# fresh_air_control.net
KiCad netlist of a schematic drawn in EAGLE
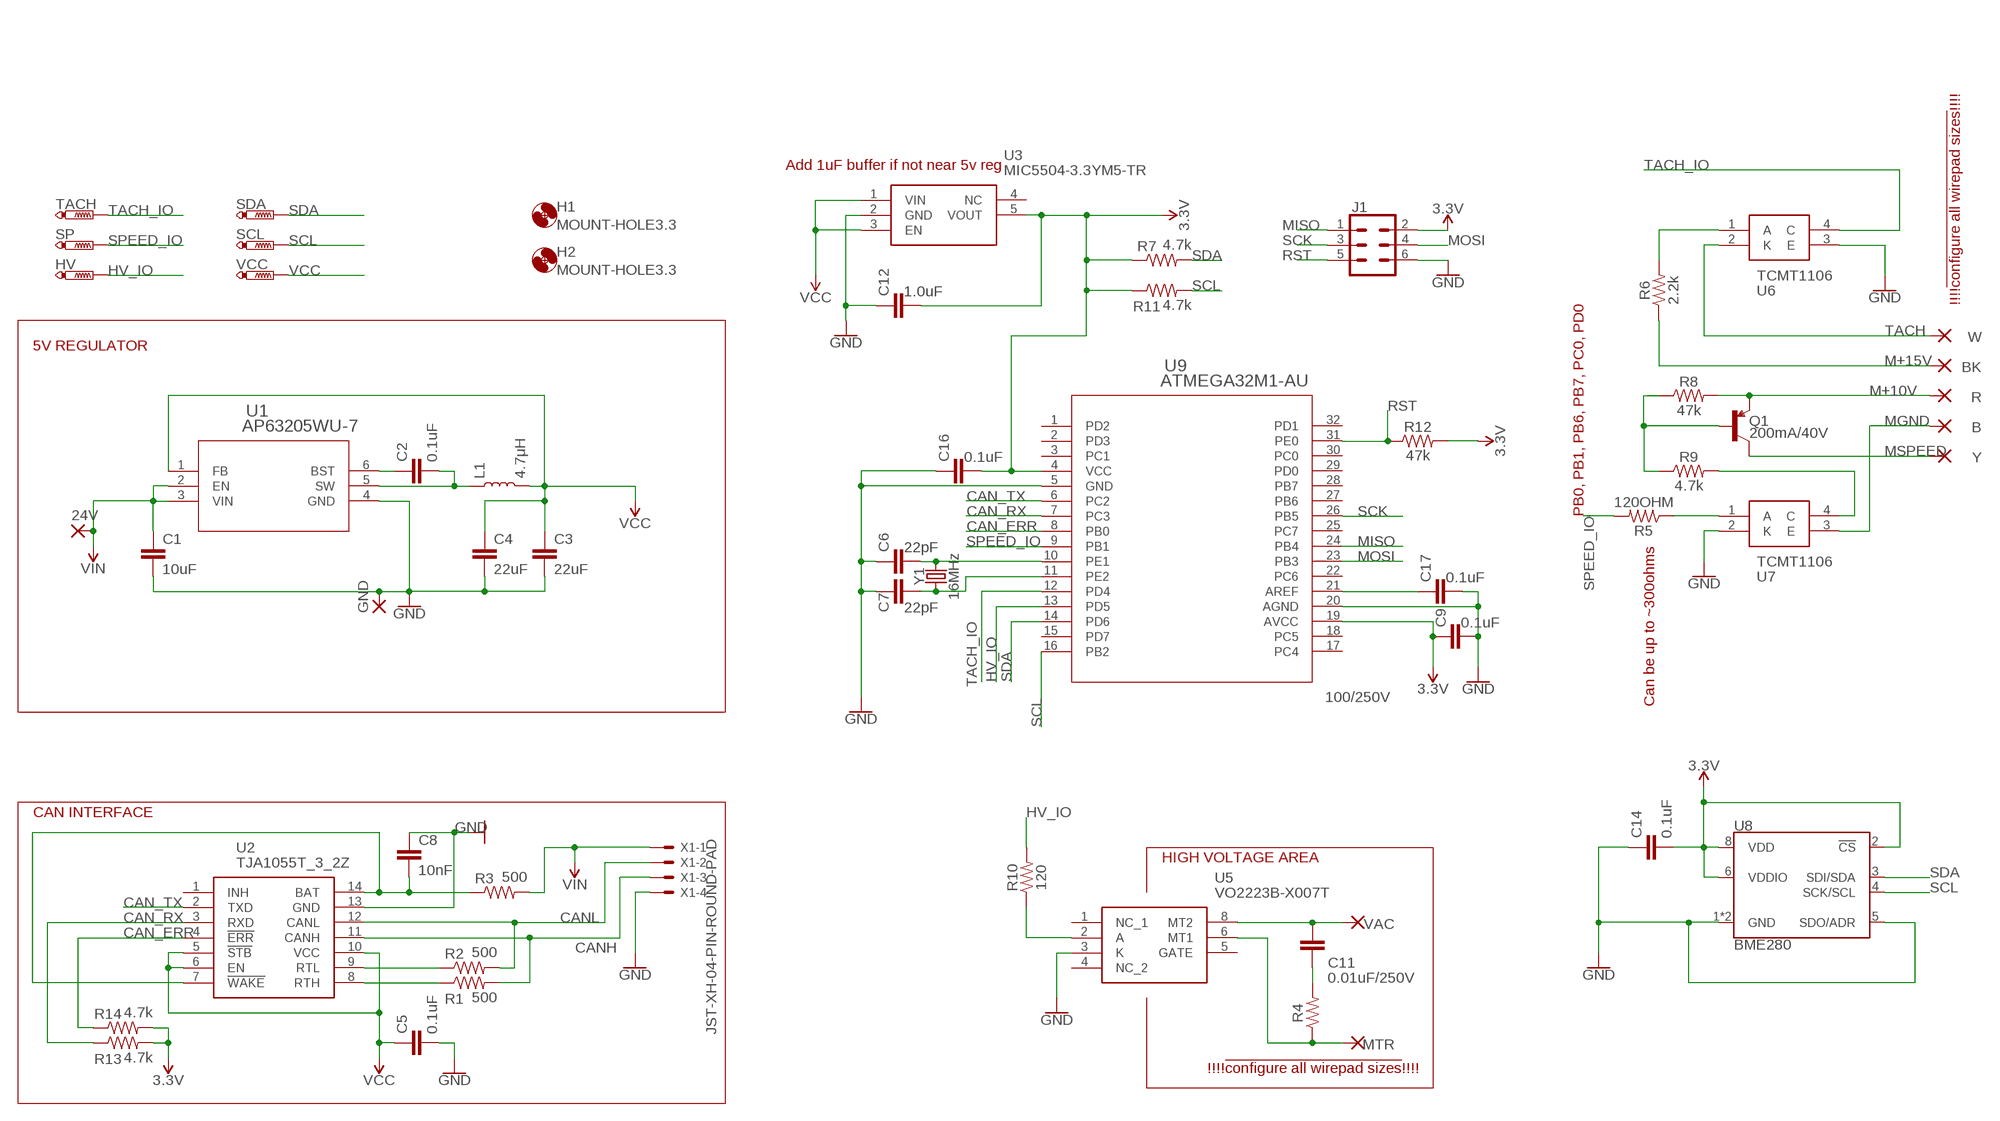
[diagram p0: schematic, sheet 1]

(export (version "E")
  (design (tool "Eeschema 10.0.6"))
  (components
    (comp (ref "24V")
      (value "2,15/1,0")
      (footprint "eagle-import:2,15_1,0")
      (libsource (lib "eagle-import") (part "2,15/1,0"))
    )
    (comp (ref "B")
      (value "1,6/0,8")
      (footprint "eagle-import:1,6_0,8")
      (libsource (lib "eagle-import") (part "1,6/0,8"))
    )
    (comp (ref "BK")
      (value "1,6/0,8")
      (footprint "eagle-import:1,6_0,8")
      (libsource (lib "eagle-import") (part "1,6/0,8"))
    )
    (comp (ref "C1")
      (value "10uF")
      (footprint "eagle-import:1210")
      (libsource (lib "eagle-import") (part "10UF-1210-50V-20%"))
    )
    (comp (ref "C2")
      (value "0.1uF")
      (footprint "eagle-import:0603")
      (libsource (lib "eagle-import") (part "0.1UF-0603-25V-5%"))
    )
    (comp (ref "C3")
      (value "22uF")
      (footprint "eagle-import:0805")
      (libsource (lib "eagle-import") (part "22UF-0805-6.3V-20%"))
    )
    (comp (ref "C4")
      (value "22uF")
      (footprint "eagle-import:0805")
      (libsource (lib "eagle-import") (part "22UF-0805-6.3V-20%"))
    )
    (comp (ref "C5")
      (value "0.1uF")
      (footprint "eagle-import:0603")
      (libsource (lib "eagle-import") (part "0.1UF-0603-25V-5%"))
    )
    (comp (ref "C6")
      (value "22pF")
      (footprint "eagle-import:0603")
      (libsource (lib "eagle-import") (part "22PF-0603-50V-5%"))
    )
    (comp (ref "C7")
      (value "22pF")
      (footprint "eagle-import:0603")
      (libsource (lib "eagle-import") (part "22PF-0603-50V-5%"))
    )
    (comp (ref "C8")
      (value "10nF")
      (footprint "eagle-import:0603")
      (libsource (lib "eagle-import") (part "10NF-0603-50V-10%"))
    )
    (comp (ref "C9")
      (value "0.1uF")
      (footprint "eagle-import:0603")
      (libsource (lib "eagle-import") (part "0.1UF-0603-25V-5%"))
    )
    (comp (ref "C11")
      (value "0.01uF/250V")
      (footprint "eagle-import:0805")
      (libsource (lib "eagle-import") (part "CAP-0805"))
    )
    (comp (ref "C12")
      (value "1.0uF")
      (footprint "eagle-import:0603")
      (libsource (lib "eagle-import") (part "1.0UF-0603-16V-10%"))
    )
    (comp (ref "C14")
      (value "0.1uF")
      (footprint "eagle-import:0603")
      (libsource (lib "eagle-import") (part "0.1UF-0603-25V-5%"))
    )
    (comp (ref "C16")
      (value "0.1uF")
      (footprint "eagle-import:0603")
      (libsource (lib "eagle-import") (part "0.1UF-0603-25V-5%"))
    )
    (comp (ref "C17")
      (value "0.1uF")
      (footprint "eagle-import:0603")
      (libsource (lib "eagle-import") (part "0.1UF-0603-25V-5%"))
    )
    (comp (ref "GND")
      (value "2,15/1,0")
      (footprint "eagle-import:2,15_1,0")
      (libsource (lib "eagle-import") (part "2,15/1,0"))
    )
    (comp (ref "H1")
      (value "MOUNT-HOLE3.3")
      (footprint "eagle-import:3,3")
      (libsource (lib "eagle-import") (part "MOUNT-HOLE3.3"))
    )
    (comp (ref "H2")
      (value "MOUNT-HOLE3.3")
      (footprint "eagle-import:3,3")
      (libsource (lib "eagle-import") (part "MOUNT-HOLE3.3"))
    )
    (comp (ref "HV")
      (value "PTR1B1,27")
      (footprint "eagle-import:B1,27")
      (libsource (lib "eagle-import") (part "PTR1B1,27"))
    )
    (comp (ref "J1")
      (value "CONN_03X2NO_SILK")
      (footprint "eagle-import:2X3-NS")
      (libsource (lib "eagle-import") (part "CONN_03X2NO_SILK"))
    )
    (comp (ref "L1")
      (value "4.7μH")
      (footprint "eagle-import:INDUCTOR_4X4MM")
      (libsource (lib "eagle-import") (part "4.7μH_SHIELDED_INDUCTORNPIS_LS"))
    )
    (comp (ref "MTR")
      (value "1,6/0,8")
      (footprint "eagle-import:1,6_0,8")
      (libsource (lib "eagle-import") (part "1,6/0,8"))
    )
    (comp (ref "Q1")
      (value "200mA/40V")
      (footprint "eagle-import:SOT23-3")
      (libsource (lib "eagle-import") (part "TRANS_PNP-PMBT3906|MMBT3906L"))
    )
    (comp (ref "R")
      (value "1,6/0,8")
      (footprint "eagle-import:1,6_0,8")
      (libsource (lib "eagle-import") (part "1,6/0,8"))
    )
    (comp (ref "R1")
      (value "500")
      (footprint "eagle-import:0603")
      (libsource (lib "eagle-import") (part "RESISTOR0603"))
    )
    (comp (ref "R2")
      (value "500")
      (footprint "eagle-import:0603")
      (libsource (lib "eagle-import") (part "RESISTOR0603"))
    )
    (comp (ref "R3")
      (value "500")
      (footprint "eagle-import:0603")
      (libsource (lib "eagle-import") (part "RESISTOR0603"))
    )
    (comp (ref "R4")
      (value "100/250V")
      (footprint "eagle-import:0805")
      (libsource (lib "eagle-import") (part "RESISTOR0805"))
    )
    (comp (ref "R5")
      (value "120OHM")
      (footprint "eagle-import:0603")
      (libsource (lib "eagle-import") (part "120OHM"))
    )
    (comp (ref "R6")
      (value "2.2k")
      (footprint "eagle-import:0603")
      (libsource (lib "eagle-import") (part "2.2KOHM-0603-1/10W-1%"))
    )
    (comp (ref "R7")
      (value "4.7k")
      (footprint "eagle-import:0603")
      (libsource (lib "eagle-import") (part "4.7KOHM-0603-1/10W-1%"))
    )
    (comp (ref "R8")
      (value "47k")
      (footprint "eagle-import:0603")
      (libsource (lib "eagle-import") (part "47KOHM-0603-1/10W-1%"))
    )
    (comp (ref "R9")
      (value "4.7k")
      (footprint "eagle-import:0603")
      (libsource (lib "eagle-import") (part "4.7KOHM-0603-1/10W-1%"))
    )
    (comp (ref "R10")
      (value "120")
      (footprint "eagle-import:0603")
      (libsource (lib "eagle-import") (part "120OHM"))
    )
    (comp (ref "R11")
      (value "4.7k")
      (footprint "eagle-import:0603")
      (libsource (lib "eagle-import") (part "4.7KOHM-0603-1/10W-1%"))
    )
    (comp (ref "R12")
      (value "47k")
      (footprint "eagle-import:0603")
      (libsource (lib "eagle-import") (part "47KOHM-0603-1/10W-1%"))
    )
    (comp (ref "R13")
      (value "4.7k")
      (footprint "eagle-import:0603")
      (libsource (lib "eagle-import") (part "4.7KOHM-0603-1/10W-1%"))
    )
    (comp (ref "R14")
      (value "4.7k")
      (footprint "eagle-import:0603")
      (libsource (lib "eagle-import") (part "4.7KOHM-0603-1/10W-1%"))
    )
    (comp (ref "SCL")
      (value "PTR1B1,27")
      (footprint "eagle-import:B1,27")
      (libsource (lib "eagle-import") (part "PTR1B1,27"))
    )
    (comp (ref "SDA")
      (value "PTR1B1,27")
      (footprint "eagle-import:B1,27")
      (libsource (lib "eagle-import") (part "PTR1B1,27"))
    )
    (comp (ref "SP")
      (value "PTR1B1,27")
      (footprint "eagle-import:B1,27")
      (libsource (lib "eagle-import") (part "PTR1B1,27"))
    )
    (comp (ref "TACH")
      (value "PTR1B1,27")
      (footprint "eagle-import:B1,27")
      (libsource (lib "eagle-import") (part "PTR1B1,27"))
    )
    (comp (ref "U1")
      (value "AP63205WU-7")
      (footprint "eagle-import:SOIC_05WU-7_DIO")
      (fields (field (name "COPYRIGHT") "Copyright (C) 2023 Ultra Librarian. All rights reserved."))
      (libsource (lib "eagle-import") (part "AP63205WU-7"))
    )
    (comp (ref "U2")
      (value "TJA1055T_3_2Z")
      (footprint "eagle-import:SOIC127P600X175-14N")
      (fields
        (field (name "MANUFACTURER_PART_NUMBER") "TJA1055T/3/2Z")
        (field (name "MOUSER_PART_NUMBER") "771-TJA1055T/3/2Z")
      )
      (libsource (lib "eagle-import") (part "TJA1055T_3_2Z"))
    )
    (comp (ref "U3")
      (value "MIC5504-3.3YM5-TR")
      (footprint "eagle-import:SOT95P280X145-5N")
      (fields (field (name "MOUSER_PART_NUMBER") "998-MIC5504-3.3YM5TR"))
      (libsource (lib "eagle-import") (part "MIC5504-3.3YM5-TR"))
    )
    (comp (ref "U5")
      (value "VO2223B-X007T")
      (footprint "eagle-import:VO2223BX007T")
      (fields (field (name "MOUSER_PART_NUMBER") "78-VO2223B-X007T"))
      (libsource (lib "eagle-import") (part "VO2223B-X007T"))
    )
    (comp (ref "U6")
      (value "TCMT1106")
      (footprint "eagle-import:SOIC127P700X230-4N")
      (fields (field (name "MOUSER_PART_NUMBER") "782-TCMT1106"))
      (libsource (lib "eagle-import") (part "TCMT1106"))
    )
    (comp (ref "U7")
      (value "TCMT1106")
      (footprint "eagle-import:SOIC127P700X230-4N")
      (fields (field (name "MOUSER_PART_NUMBER") "782-TCMT1106"))
      (libsource (lib "eagle-import") (part "TCMT1106"))
    )
    (comp (ref "U8")
      (value "BME280")
      (footprint "eagle-import:LGA-8-2.5X2.5")
      (libsource (lib "eagle-import") (part "BME280"))
    )
    (comp (ref "U9")
      (value "ATMEGA32M1-AU")
      (footprint "eagle-import:32A_ATM")
      (fields (field (name "COPYRIGHT") "Copyright (C) 2023 Ultra Librarian. All rights reserved."))
      (libsource (lib "eagle-import") (part "ATMEGA32M1-AU"))
    )
    (comp (ref "VAC")
      (value "1,6/0,8")
      (footprint "eagle-import:1,6_0,8")
      (libsource (lib "eagle-import") (part "1,6/0,8"))
    )
    (comp (ref "VCC")
      (value "PTR1B1,27")
      (footprint "eagle-import:B1,27")
      (libsource (lib "eagle-import") (part "PTR1B1,27"))
    )
    (comp (ref "W")
      (value "1,6/0,8")
      (footprint "eagle-import:1,6_0,8")
      (libsource (lib "eagle-import") (part "1,6/0,8"))
    )
    (comp (ref "X1")
      (value "JST-XH-04-PIN-ROUND-PAD")
      (footprint "eagle-import:JST-XH-04-PACKAGE-ROUND-PAD")
      (libsource (lib "eagle-import") (part "JST-XH-04-PIN-ROUND-PAD"))
    )
    (comp (ref "Y")
      (value "1,6/0,8")
      (footprint "eagle-import:1,6_0,8")
      (libsource (lib "eagle-import") (part "1,6/0,8"))
    )
    (comp (ref "Y1")
      (value "16MHz")
      (footprint "eagle-import:CRYSTAL-SMD-5X3.2-4PAD")
      (libsource (lib "eagle-import") (part "CRYSTAL-16MHZSMD-5X3.2"))
    )
  )
  (nets
    (net (code "1") (name "/CANH") (class "Default")
      (node (ref "R1") (pin "2") (pinfunction "2_2") (pintype "passive"))
      (node (ref "U2") (pin "11") (pinfunction "CANH_11") (pintype "bidirectional"))
      (node (ref "X1") (pin "3") (pinfunction "S_3") (pintype "passive"))
    )
    (net (code "2") (name "/CANL") (class "Default")
      (node (ref "R2") (pin "2") (pinfunction "2_2") (pintype "passive"))
      (node (ref "U2") (pin "12") (pinfunction "CANL_12") (pintype "bidirectional"))
      (node (ref "X1") (pin "2") (pinfunction "S_2") (pintype "passive"))
    )
    (net (code "3") (name "/CAN_ERR") (class "Default")
      (node (ref "R14") (pin "1") (pinfunction "1_1") (pintype "passive"))
      (node (ref "U2") (pin "4") (pinfunction "~{ERR}_4") (pintype "bidirectional"))
      (node (ref "U9") (pin "8") (pinfunction "PB0_8") (pintype "bidirectional"))
    )
    (net (code "4") (name "/CAN_RX") (class "Default")
      (node (ref "R13") (pin "1") (pinfunction "1_1") (pintype "passive"))
      (node (ref "U2") (pin "3") (pinfunction "RXD_3") (pintype "bidirectional"))
      (node (ref "U9") (pin "7") (pinfunction "PC3_7") (pintype "bidirectional"))
    )
    (net (code "5") (name "/CAN_TX") (class "Default")
      (node (ref "U2") (pin "2") (pinfunction "TXD_2") (pintype "bidirectional"))
      (node (ref "U9") (pin "6") (pinfunction "PC2_6") (pintype "bidirectional"))
    )
    (net (code "6") (name "/HV_IO") (class "Default")
      (node (ref "HV") (pin "TP") (pinfunction "TP_TP") (pintype "input"))
      (node (ref "R10") (pin "2") (pinfunction "2_2") (pintype "passive"))
      (node (ref "U9") (pin "13") (pinfunction "PD5_13") (pintype "bidirectional"))
    )
    (net (code "7") (name "/M+10V") (class "Default")
      (node (ref "Q1") (pin "2") (pinfunction "E_2") (pintype "passive"))
      (node (ref "R") (pin "1") (pinfunction "P_1") (pintype "passive"))
      (node (ref "R8") (pin "2") (pinfunction "2_2") (pintype "passive"))
    )
    (net (code "8") (name "/M+15V") (class "Default")
      (node (ref "BK") (pin "1") (pinfunction "P_1") (pintype "passive"))
      (node (ref "R6") (pin "1") (pinfunction "1_1") (pintype "passive"))
    )
    (net (code "9") (name "/MGND") (class "Default")
      (node (ref "B") (pin "1") (pinfunction "P_1") (pintype "passive"))
      (node (ref "U7") (pin "3") (pinfunction "E_3") (pintype "bidirectional"))
    )
    (net (code "10") (name "/MISO") (class "Default")
      (node (ref "J1") (pin "1") (pinfunction "1_1") (pintype "bidirectional"))
      (node (ref "U9") (pin "24") (pinfunction "PB4_24") (pintype "bidirectional"))
    )
    (net (code "11") (name "/MOSI") (class "Default")
      (node (ref "J1") (pin "4") (pinfunction "4_4") (pintype "bidirectional"))
      (node (ref "U9") (pin "23") (pinfunction "PB3_23") (pintype "bidirectional"))
    )
    (net (code "12") (name "/MSPEED") (class "Default")
      (node (ref "Q1") (pin "3") (pinfunction "C_3") (pintype "passive"))
      (node (ref "Y") (pin "1") (pinfunction "P_1") (pintype "passive"))
    )
    (net (code "13") (name "/RST") (class "Default")
      (node (ref "J1") (pin "5") (pinfunction "5_5") (pintype "bidirectional"))
      (node (ref "R12") (pin "1") (pinfunction "1_1") (pintype "passive"))
      (node (ref "U9") (pin "31") (pinfunction "PE0_31") (pintype "bidirectional"))
    )
    (net (code "14") (name "/SCK") (class "Default")
      (node (ref "J1") (pin "3") (pinfunction "3_3") (pintype "bidirectional"))
      (node (ref "U9") (pin "26") (pinfunction "PB5_26") (pintype "bidirectional"))
    )
    (net (code "15") (name "/SCL") (class "Default")
      (node (ref "R11") (pin "2") (pinfunction "2_2") (pintype "passive"))
      (node (ref "SCL") (pin "TP") (pinfunction "TP_TP") (pintype "input"))
      (node (ref "U8") (pin "4") (pinfunction "SCK/SCL_4") (pintype "bidirectional"))
      (node (ref "U9") (pin "16") (pinfunction "PB2_16") (pintype "bidirectional"))
    )
    (net (code "16") (name "/SDA") (class "Default")
      (node (ref "R7") (pin "2") (pinfunction "2_2") (pintype "passive"))
      (node (ref "SDA") (pin "TP") (pinfunction "TP_TP") (pintype "input"))
      (node (ref "U8") (pin "3") (pinfunction "SDI/SDA_3") (pintype "bidirectional"))
      (node (ref "U9") (pin "14") (pinfunction "PD6_14") (pintype "bidirectional"))
    )
    (net (code "17") (name "/SPEED_IO") (class "Default")
      (node (ref "R5") (pin "2") (pinfunction "2_2") (pintype "passive"))
      (node (ref "SP") (pin "TP") (pinfunction "TP_TP") (pintype "input"))
      (node (ref "U9") (pin "9") (pinfunction "PB1_9") (pintype "bidirectional"))
    )
    (net (code "18") (name "/TACH") (class "Default")
      (node (ref "U6") (pin "2") (pinfunction "K_2") (pintype "bidirectional"))
      (node (ref "W") (pin "1") (pinfunction "P_1") (pintype "passive"))
    )
    (net (code "19") (name "/TACH_IO") (class "Default")
      (node (ref "TACH") (pin "TP") (pinfunction "TP_TP") (pintype "input"))
      (node (ref "U6") (pin "4") (pinfunction "C_4") (pintype "bidirectional"))
      (node (ref "U9") (pin "12") (pinfunction "PD4_12") (pintype "bidirectional"))
    )
    (net (code "20") (name "3.3V") (class "Default")
      (node (ref "C12") (pin "2") (pinfunction "2_2") (pintype "passive"))
      (node (ref "C14") (pin "2") (pinfunction "2_2") (pintype "passive"))
      (node (ref "C16") (pin "2") (pinfunction "2_2") (pintype "passive"))
      (node (ref "C9") (pin "1") (pinfunction "1_1") (pintype "passive"))
      (node (ref "J1") (pin "2") (pinfunction "2_2") (pintype "bidirectional"))
      (node (ref "R11") (pin "1") (pinfunction "1_1") (pintype "passive"))
      (node (ref "R12") (pin "2") (pinfunction "2_2") (pintype "passive"))
      (node (ref "R13") (pin "2") (pinfunction "2_2") (pintype "passive"))
      (node (ref "R14") (pin "2") (pinfunction "2_2") (pintype "passive"))
      (node (ref "R7") (pin "1") (pinfunction "1_1") (pintype "passive"))
      (node (ref "U3") (pin "5") (pinfunction "VOUT_5") (pintype "bidirectional"))
      (node (ref "U8") (pin "2") (pinfunction "~{CS}_2") (pintype "bidirectional"))
      (node (ref "U8") (pin "6") (pinfunction "VDDIO_6") (pintype "bidirectional"))
      (node (ref "U8") (pin "8") (pinfunction "VDD_8") (pintype "bidirectional"))
      (node (ref "U9") (pin "19") (pinfunction "AVCC_19") (pintype "power_in"))
      (node (ref "U9") (pin "4") (pinfunction "VCC_4") (pintype "power_in"))
    )
    (net (code "21") (name "GND") (class "Default")
      (node (ref "C1") (pin "2") (pinfunction "2_2") (pintype "passive"))
      (node (ref "C12") (pin "1") (pinfunction "1_1") (pintype "passive"))
      (node (ref "C14") (pin "1") (pinfunction "1_1") (pintype "passive"))
      (node (ref "C16") (pin "1") (pinfunction "1_1") (pintype "passive"))
      (node (ref "C17") (pin "2") (pinfunction "2_2") (pintype "passive"))
      (node (ref "C3") (pin "2") (pinfunction "2_2") (pintype "passive"))
      (node (ref "C4") (pin "2") (pinfunction "2_2") (pintype "passive"))
      (node (ref "C5") (pin "2") (pinfunction "2_2") (pintype "passive"))
      (node (ref "C6") (pin "1") (pinfunction "1_1") (pintype "passive"))
      (node (ref "C7") (pin "1") (pinfunction "1_1") (pintype "passive"))
      (node (ref "C8") (pin "1") (pinfunction "1_1") (pintype "passive"))
      (node (ref "C9") (pin "2") (pinfunction "2_2") (pintype "passive"))
      (node (ref "GND") (pin "1") (pinfunction "P_1") (pintype "passive"))
      (node (ref "J1") (pin "6") (pinfunction "6_6") (pintype "bidirectional"))
      (node (ref "U1") (pin "4") (pinfunction "GND_4") (pintype "passive"))
      (node (ref "U2") (pin "13") (pinfunction "GND_13") (pintype "bidirectional"))
      (node (ref "U3") (pin "2") (pinfunction "GND_2") (pintype "bidirectional"))
      (node (ref "U5") (pin "3") (pinfunction "K_3") (pintype "bidirectional"))
      (node (ref "U6") (pin "3") (pinfunction "E_3") (pintype "bidirectional"))
      (node (ref "U7") (pin "2") (pinfunction "K_2") (pintype "bidirectional"))
      (node (ref "U8") (pin "1") (pinfunction "GND_1") (pintype "bidirectional"))
      (node (ref "U8") (pin "5") (pinfunction "SDO/ADR_5") (pintype "bidirectional"))
      (node (ref "U8") (pin "7") (pinfunction "GND_7") (pintype "bidirectional"))
      (node (ref "U9") (pin "20") (pinfunction "AGND_20") (pintype "power_in"))
      (node (ref "U9") (pin "5") (pinfunction "GND_5") (pintype "power_in"))
      (node (ref "X1") (pin "4") (pinfunction "S_4") (pintype "passive"))
    )
    (net (code "22") (name "Net-(C11-Pad2)") (class "Default")
      (node (ref "C11") (pin "2") (pinfunction "2_2") (pintype "passive"))
      (node (ref "R4") (pin "2") (pinfunction "2_2") (pintype "passive"))
    )
    (net (code "23") (name "Net-(L1-1)") (class "Default")
      (node (ref "C2") (pin "2") (pinfunction "2_2") (pintype "passive"))
      (node (ref "L1") (pin "P$1") (pinfunction "1_P$1") (pintype "passive"))
      (node (ref "U1") (pin "5") (pinfunction "SW_5") (pintype "passive"))
    )
    (net (code "24") (name "Net-(MTR-P)") (class "Default")
      (node (ref "MTR") (pin "1") (pinfunction "P_1") (pintype "passive"))
      (node (ref "R4") (pin "1") (pinfunction "1_1") (pintype "passive"))
      (node (ref "U5") (pin "6") (pinfunction "MT1_6") (pintype "bidirectional"))
    )
    (net (code "25") (name "Net-(Q1-B)") (class "Default")
      (node (ref "Q1") (pin "1") (pinfunction "B_1") (pintype "passive"))
      (node (ref "R8") (pin "1") (pinfunction "1_1") (pintype "passive"))
      (node (ref "R9") (pin "1") (pinfunction "1_1") (pintype "passive"))
    )
    (net (code "26") (name "Net-(U1-BST)") (class "Default")
      (node (ref "C2") (pin "1") (pinfunction "1_1") (pintype "passive"))
      (node (ref "U1") (pin "6") (pinfunction "BST_6") (pintype "passive"))
    )
    (net (code "27") (name "Net-(U2-BAT)") (class "Default")
      (node (ref "C8") (pin "2") (pinfunction "2_2") (pintype "passive"))
      (node (ref "R3") (pin "1") (pinfunction "1_1") (pintype "passive"))
      (node (ref "U2") (pin "14") (pinfunction "BAT_14") (pintype "bidirectional"))
      (node (ref "U2") (pin "7") (pinfunction "~{WAKE}_7") (pintype "bidirectional"))
    )
    (net (code "28") (name "Net-(U2-RTH)") (class "Default")
      (node (ref "R1") (pin "1") (pinfunction "1_1") (pintype "passive"))
      (node (ref "U2") (pin "8") (pinfunction "RTH_8") (pintype "bidirectional"))
    )
    (net (code "29") (name "Net-(U2-RTL)") (class "Default")
      (node (ref "R2") (pin "1") (pinfunction "1_1") (pintype "passive"))
      (node (ref "U2") (pin "9") (pinfunction "RTL_9") (pintype "bidirectional"))
    )
    (net (code "30") (name "Net-(U5-A)") (class "Default")
      (node (ref "R10") (pin "1") (pinfunction "1_1") (pintype "passive"))
      (node (ref "U5") (pin "2") (pinfunction "A_2") (pintype "bidirectional"))
    )
    (net (code "31") (name "Net-(U5-MT2)") (class "Default")
      (node (ref "C11") (pin "1") (pinfunction "1_1") (pintype "passive"))
      (node (ref "U5") (pin "8") (pinfunction "MT2_8") (pintype "bidirectional"))
      (node (ref "VAC") (pin "1") (pinfunction "P_1") (pintype "passive"))
    )
    (net (code "32") (name "Net-(U6-A)") (class "Default")
      (node (ref "R6") (pin "2") (pinfunction "2_2") (pintype "passive"))
      (node (ref "U6") (pin "1") (pinfunction "A_1") (pintype "bidirectional"))
    )
    (net (code "33") (name "Net-(U7-A)") (class "Default")
      (node (ref "R5") (pin "1") (pinfunction "1_1") (pintype "passive"))
      (node (ref "U7") (pin "1") (pinfunction "A_1") (pintype "bidirectional"))
    )
    (net (code "34") (name "Net-(U7-C)") (class "Default")
      (node (ref "R9") (pin "2") (pinfunction "2_2") (pintype "passive"))
      (node (ref "U7") (pin "4") (pinfunction "C_4") (pintype "bidirectional"))
    )
    (net (code "35") (name "Net-(U9-AREF)") (class "Default")
      (node (ref "C17") (pin "1") (pinfunction "1_1") (pintype "passive"))
      (node (ref "U9") (pin "21") (pinfunction "AREF_21") (pintype "passive"))
    )
    (net (code "36") (name "Net-(U9-PE1)") (class "Default")
      (node (ref "C6") (pin "2") (pinfunction "2_2") (pintype "passive"))
      (node (ref "U9") (pin "10") (pinfunction "PE1_10") (pintype "bidirectional"))
      (node (ref "Y1") (pin "3") (pinfunction "2_3") (pintype "passive"))
    )
    (net (code "37") (name "Net-(U9-PE2)") (class "Default")
      (node (ref "C7") (pin "2") (pinfunction "2_2") (pintype "passive"))
      (node (ref "U9") (pin "11") (pinfunction "PE2_11") (pintype "bidirectional"))
      (node (ref "Y1") (pin "1") (pinfunction "1_1") (pintype "passive"))
    )
    (net (code "38") (name "VCC") (class "Default")
      (node (ref "C3") (pin "1") (pinfunction "1_1") (pintype "passive"))
      (node (ref "C4") (pin "1") (pinfunction "1_1") (pintype "passive"))
      (node (ref "C5") (pin "1") (pinfunction "1_1") (pintype "passive"))
      (node (ref "L1") (pin "P$2") (pinfunction "2_P$2") (pintype "passive"))
      (node (ref "U1") (pin "1") (pinfunction "FB_1") (pintype "passive"))
      (node (ref "U2") (pin "10") (pinfunction "VCC_10") (pintype "bidirectional"))
      (node (ref "U2") (pin "5") (pinfunction "~{STB}_5") (pintype "bidirectional"))
      (node (ref "U2") (pin "6") (pinfunction "EN_6") (pintype "bidirectional"))
      (node (ref "U3") (pin "1") (pinfunction "VIN_1") (pintype "bidirectional"))
      (node (ref "U3") (pin "3") (pinfunction "EN_3") (pintype "bidirectional"))
      (node (ref "VCC") (pin "TP") (pinfunction "TP_TP") (pintype "input"))
    )
    (net (code "39") (name "VIN") (class "Default")
      (node (ref "24V") (pin "1") (pinfunction "P_1") (pintype "passive"))
      (node (ref "C1") (pin "1") (pinfunction "1_1") (pintype "passive"))
      (node (ref "R3") (pin "2") (pinfunction "2_2") (pintype "passive"))
      (node (ref "U1") (pin "2") (pinfunction "EN_2") (pintype "passive"))
      (node (ref "U1") (pin "3") (pinfunction "VIN_3") (pintype "passive"))
      (node (ref "X1") (pin "1") (pinfunction "S_1") (pintype "passive"))
    )
    (net (code "40") (name "unconnected-(U2-INH-Pad1)") (class "Default")
      (node (ref "U2") (pin "1") (pinfunction "INH_1") (pintype "bidirectional"))
    )
    (net (code "41") (name "unconnected-(U3-NC-Pad4)") (class "Default")
      (node (ref "U3") (pin "4") (pinfunction "NC_4") (pintype "no_connect"))
    )
    (net (code "42") (name "unconnected-(U5-GATE-Pad5)") (class "Default")
      (node (ref "U5") (pin "5") (pinfunction "GATE_5") (pintype "bidirectional"))
    )
    (net (code "43") (name "unconnected-(U5-NC_1-Pad1)") (class "Default")
      (node (ref "U5") (pin "1") (pinfunction "NC_1_1") (pintype "bidirectional"))
    )
    (net (code "44") (name "unconnected-(U5-NC_2-Pad4)") (class "Default")
      (node (ref "U5") (pin "4") (pinfunction "NC_2_4") (pintype "bidirectional"))
    )
    (net (code "45") (name "unconnected-(U9-PB6-Pad27)") (class "Default")
      (node (ref "U9") (pin "27") (pinfunction "PB6_27") (pintype "bidirectional"))
    )
    (net (code "46") (name "unconnected-(U9-PB7-Pad28)") (class "Default")
      (node (ref "U9") (pin "28") (pinfunction "PB7_28") (pintype "bidirectional"))
    )
    (net (code "47") (name "unconnected-(U9-PC0-Pad30)") (class "Default")
      (node (ref "U9") (pin "30") (pinfunction "PC0_30") (pintype "bidirectional"))
    )
    (net (code "48") (name "unconnected-(U9-PC1-Pad3)") (class "Default")
      (node (ref "U9") (pin "3") (pinfunction "PC1_3") (pintype "bidirectional"))
    )
    (net (code "49") (name "unconnected-(U9-PC4-Pad17)") (class "Default")
      (node (ref "U9") (pin "17") (pinfunction "PC4_17") (pintype "bidirectional"))
    )
    (net (code "50") (name "unconnected-(U9-PC5-Pad18)") (class "Default")
      (node (ref "U9") (pin "18") (pinfunction "PC5_18") (pintype "bidirectional"))
    )
    (net (code "51") (name "unconnected-(U9-PC6-Pad22)") (class "Default")
      (node (ref "U9") (pin "22") (pinfunction "PC6_22") (pintype "bidirectional"))
    )
    (net (code "52") (name "unconnected-(U9-PC7-Pad25)") (class "Default")
      (node (ref "U9") (pin "25") (pinfunction "PC7_25") (pintype "bidirectional"))
    )
    (net (code "53") (name "unconnected-(U9-PD0-Pad29)") (class "Default")
      (node (ref "U9") (pin "29") (pinfunction "PD0_29") (pintype "bidirectional"))
    )
    (net (code "54") (name "unconnected-(U9-PD1-Pad32)") (class "Default")
      (node (ref "U9") (pin "32") (pinfunction "PD1_32") (pintype "bidirectional"))
    )
    (net (code "55") (name "unconnected-(U9-PD2-Pad1)") (class "Default")
      (node (ref "U9") (pin "1") (pinfunction "PD2_1") (pintype "bidirectional"))
    )
    (net (code "56") (name "unconnected-(U9-PD3-Pad2)") (class "Default")
      (node (ref "U9") (pin "2") (pinfunction "PD3_2") (pintype "bidirectional"))
    )
    (net (code "57") (name "unconnected-(U9-PD7-Pad15)") (class "Default")
      (node (ref "U9") (pin "15") (pinfunction "PD7_15") (pintype "bidirectional"))
    )
  )
)
